# PixiFlood_1_8_PTH.net
KiCad netlist of a schematic drawn in EAGLE
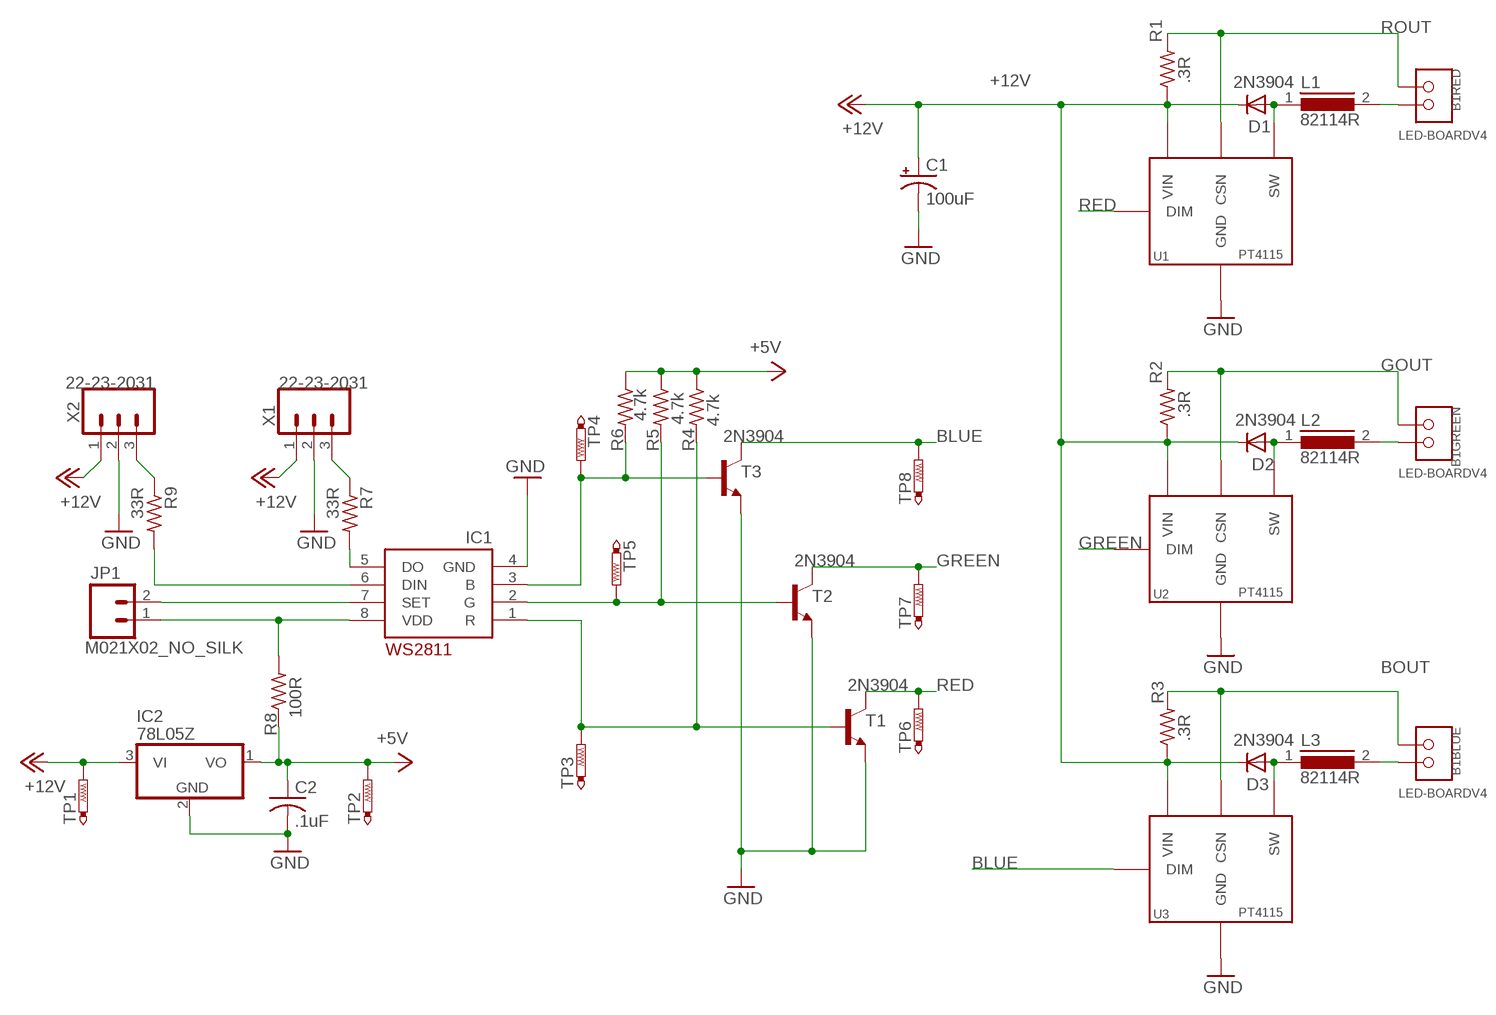
[diagram p0: schematic, sheet 1]

(export (version "E")
  (design (tool "Eeschema 10.0.6"))
  (components
    (comp (ref "B1")
      (value "LED-BOARDV4")
      (footprint "eagle-import:LED_BOARD-V4")
      (libsource (lib "eagle-import") (part "LED-BOARDV4"))
    )
    (comp (ref "C1")
      (value "100uF")
      (footprint "eagle-import:TT2D6L")
      (libsource (lib "eagle-import") (part "CPOL-USTT2D6L"))
    )
    (comp (ref "C2")
      (value ".1uF")
      (footprint "eagle-import:C050-024X044")
      (libsource (lib "eagle-import") (part "C-US050-024X044"))
    )
    (comp (ref "D1")
      (value "2N3904")
      (footprint "eagle-import:DO07")
      (libsource (lib "eagle-import") (part "DIODE-DO07"))
    )
    (comp (ref "D2")
      (value "2N3904")
      (footprint "eagle-import:DO07")
      (libsource (lib "eagle-import") (part "DIODE-DO07"))
    )
    (comp (ref "D3")
      (value "2N3904")
      (footprint "eagle-import:DO07")
      (libsource (lib "eagle-import") (part "DIODE-DO07"))
    )
    (comp (ref "IC1")
      (value "WS2811-SOP8")
      (footprint "eagle-import:SO08-SKINNYPADS")
      (libsource (lib "eagle-import") (part "WS2811-SOP8"))
    )
    (comp (ref "IC2")
      (value "78L05Z")
      (footprint "eagle-import:TO92")
      (libsource (lib "eagle-import") (part "78ZL05"))
    )
    (comp (ref "JP1")
      (value "M021X02_NO_SILK")
      (footprint "eagle-import:1X02_NO_SILK")
      (libsource (lib "eagle-import") (part "M021X02_NO_SILK"))
    )
    (comp (ref "L1")
      (value "82114R")
      (footprint "eagle-import:82114R")
      (libsource (lib "eagle-import") (part "82114R"))
    )
    (comp (ref "L2")
      (value "82114R")
      (footprint "eagle-import:82114R")
      (libsource (lib "eagle-import") (part "82114R"))
    )
    (comp (ref "L3")
      (value "82114R")
      (footprint "eagle-import:82114R")
      (libsource (lib "eagle-import") (part "82114R"))
    )
    (comp (ref "R1")
      (value ".3R")
      (footprint "eagle-import:0204_7")
      (libsource (lib "eagle-import") (part "resistor_R-US_0204/7"))
    )
    (comp (ref "R2")
      (value ".3R")
      (footprint "eagle-import:0204_7")
      (libsource (lib "eagle-import") (part "resistor_R-US_0204/7"))
    )
    (comp (ref "R3")
      (value ".3R")
      (footprint "eagle-import:0204_7")
      (libsource (lib "eagle-import") (part "resistor_R-US_0204/7"))
    )
    (comp (ref "R4")
      (value "4.7k")
      (footprint "eagle-import:0204_7")
      (libsource (lib "eagle-import") (part "resistor_R-US_0204/7"))
    )
    (comp (ref "R5")
      (value "4.7k")
      (footprint "eagle-import:0204_7")
      (libsource (lib "eagle-import") (part "resistor_R-US_0204/7"))
    )
    (comp (ref "R6")
      (value "4.7k")
      (footprint "eagle-import:0204_7")
      (libsource (lib "eagle-import") (part "resistor_R-US_0204/7"))
    )
    (comp (ref "R7")
      (value "33R")
      (footprint "eagle-import:0204_7")
      (libsource (lib "eagle-import") (part "R-US_0204/7"))
    )
    (comp (ref "R8")
      (value "100R")
      (footprint "eagle-import:0204_7")
      (libsource (lib "eagle-import") (part "R-US_0204/7"))
    )
    (comp (ref "R9")
      (value "33R")
      (footprint "eagle-import:0204_7")
      (libsource (lib "eagle-import") (part "R-US_0204/7"))
    )
    (comp (ref "T1")
      (value "2N3904")
      (footprint "eagle-import:TO92")
      (libsource (lib "eagle-import") (part "2N3904"))
    )
    (comp (ref "T2")
      (value "2N3904")
      (footprint "eagle-import:TO92")
      (libsource (lib "eagle-import") (part "2N3904"))
    )
    (comp (ref "T3")
      (value "2N3904")
      (footprint "eagle-import:TO92")
      (libsource (lib "eagle-import") (part "2N3904"))
    )
    (comp (ref "TP1")
      (value "PTR1B2,54")
      (footprint "eagle-import:B2,54")
      (libsource (lib "eagle-import") (part "PTR1B2,54"))
    )
    (comp (ref "TP2")
      (value "PTR1B2,54")
      (footprint "eagle-import:B2,54")
      (libsource (lib "eagle-import") (part "PTR1B2,54"))
    )
    (comp (ref "TP3")
      (value "PTR1B1,27")
      (footprint "eagle-import:B1,27")
      (libsource (lib "eagle-import") (part "PTR1B1,27"))
    )
    (comp (ref "TP4")
      (value "PTR1B1,27")
      (footprint "eagle-import:B1,27")
      (libsource (lib "eagle-import") (part "PTR1B1,27"))
    )
    (comp (ref "TP5")
      (value "PTR1B1,27")
      (footprint "eagle-import:B1,27")
      (libsource (lib "eagle-import") (part "PTR1B1,27"))
    )
    (comp (ref "TP6")
      (value "PTR1B1,27")
      (footprint "eagle-import:B1,27")
      (libsource (lib "eagle-import") (part "PTR1B1,27"))
    )
    (comp (ref "TP7")
      (value "PTR1B1,27")
      (footprint "eagle-import:B1,27")
      (libsource (lib "eagle-import") (part "PTR1B1,27"))
    )
    (comp (ref "TP8")
      (value "PTR1B1,27")
      (footprint "eagle-import:B1,27")
      (libsource (lib "eagle-import") (part "PTR1B1,27"))
    )
    (comp (ref "U1")
      (value "PT4115B89E")
      (footprint "eagle-import:SOT89-5")
      (libsource (lib "eagle-import") (part "PT4115B89E"))
    )
    (comp (ref "U2")
      (value "PT4115B89E")
      (footprint "eagle-import:SOT89-5")
      (libsource (lib "eagle-import") (part "PT4115B89E"))
    )
    (comp (ref "U3")
      (value "PT4115B89E")
      (footprint "eagle-import:SOT89-5")
      (libsource (lib "eagle-import") (part "PT4115B89E"))
    )
    (comp (ref "X1")
      (value "22-23-2031")
      (footprint "eagle-import:22-23-2031")
      (fields (field (name "MF") "MOLEX"))
      (libsource (lib "eagle-import") (part "22-23-2031"))
    )
    (comp (ref "X2")
      (value "22-23-2031")
      (footprint "eagle-import:22-23-2031")
      (fields (field (name "MF") "MOLEX"))
      (libsource (lib "eagle-import") (part "22-23-2031"))
    )
  )
  (nets
    (net (code "1") (name "+5V") (class "Default")
      (node (ref "C2") (pin "1") (pinfunction "1_1") (pintype "passive"))
      (node (ref "IC2") (pin "1") (pinfunction "VO_1") (pintype "passive"))
      (node (ref "R4") (pin "1") (pinfunction "1_1") (pintype "passive"))
      (node (ref "R5") (pin "1") (pinfunction "1_1") (pintype "passive"))
      (node (ref "R6") (pin "1") (pinfunction "1_1") (pintype "passive"))
      (node (ref "R8") (pin "1") (pinfunction "1_1") (pintype "passive"))
      (node (ref "TP2") (pin "TP") (pinfunction "TP_TP") (pintype "input"))
    )
    (net (code "2") (name "+12V") (class "Default")
      (node (ref "C1") (pin "+") (pinfunction "+_+") (pintype "passive"))
      (node (ref "D1") (pin "C") (pinfunction "C_C") (pintype "passive"))
      (node (ref "D2") (pin "C") (pinfunction "C_C") (pintype "passive"))
      (node (ref "D3") (pin "C") (pinfunction "C_C") (pintype "passive"))
      (node (ref "IC2") (pin "3") (pinfunction "VI_3") (pintype "input"))
      (node (ref "R1") (pin "1") (pinfunction "1_1") (pintype "passive"))
      (node (ref "R2") (pin "1") (pinfunction "1_1") (pintype "passive"))
      (node (ref "R3") (pin "1") (pinfunction "1_1") (pintype "passive"))
      (node (ref "TP1") (pin "TP") (pinfunction "TP_TP") (pintype "input"))
      (node (ref "U1") (pin "5") (pinfunction "VIN_5") (pintype "power_in"))
      (node (ref "U2") (pin "5") (pinfunction "VIN_5") (pintype "power_in"))
      (node (ref "U3") (pin "5") (pinfunction "VIN_5") (pintype "power_in"))
      (node (ref "X1") (pin "1") (pinfunction "1_1") (pintype "passive"))
      (node (ref "X2") (pin "1") (pinfunction "1_1") (pintype "passive"))
    )
    (net (code "3") (name "/BLUE") (class "Default")
      (node (ref "T3") (pin "1") (pinfunction "C_1") (pintype "passive"))
      (node (ref "TP8") (pin "TP") (pinfunction "TP_TP") (pintype "input"))
      (node (ref "U3") (pin "3") (pinfunction "DIM_3") (pintype "bidirectional"))
    )
    (net (code "4") (name "/BOUT") (class "Default")
      (node (ref "B1") (pin "B+") (pinfunction "P$2_B+") (pintype "bidirectional"))
      (node (ref "B1") (pin "B+@2") (pinfunction "P$2_B+@2") (pintype "bidirectional"))
      (node (ref "R3") (pin "2") (pinfunction "2_2") (pintype "passive"))
      (node (ref "U3") (pin "4") (pinfunction "CSN_4") (pintype "bidirectional"))
    )
    (net (code "5") (name "/GOUT") (class "Default")
      (node (ref "B1") (pin "G+") (pinfunction "P$2_G+") (pintype "bidirectional"))
      (node (ref "B1") (pin "G+@1") (pinfunction "P$2_G+@1") (pintype "bidirectional"))
      (node (ref "R2") (pin "2") (pinfunction "2_2") (pintype "passive"))
      (node (ref "U2") (pin "4") (pinfunction "CSN_4") (pintype "bidirectional"))
    )
    (net (code "6") (name "/GREEN") (class "Default")
      (node (ref "T2") (pin "1") (pinfunction "C_1") (pintype "passive"))
      (node (ref "TP7") (pin "TP") (pinfunction "TP_TP") (pintype "input"))
      (node (ref "U2") (pin "3") (pinfunction "DIM_3") (pintype "bidirectional"))
    )
    (net (code "7") (name "/RED") (class "Default")
      (node (ref "T1") (pin "1") (pinfunction "C_1") (pintype "passive"))
      (node (ref "TP6") (pin "TP") (pinfunction "TP_TP") (pintype "input"))
      (node (ref "U1") (pin "3") (pinfunction "DIM_3") (pintype "bidirectional"))
    )
    (net (code "8") (name "/ROUT") (class "Default")
      (node (ref "B1") (pin "R+") (pinfunction "P$2_R+") (pintype "bidirectional"))
      (node (ref "B1") (pin "R+@1") (pinfunction "P$2_R+@1") (pintype "bidirectional"))
      (node (ref "R1") (pin "2") (pinfunction "2_2") (pintype "passive"))
      (node (ref "U1") (pin "4") (pinfunction "CSN_4") (pintype "bidirectional"))
    )
    (net (code "9") (name "GND") (class "Default")
      (node (ref "C1") (pin "-") (pinfunction "-_-") (pintype "passive"))
      (node (ref "C2") (pin "2") (pinfunction "2_2") (pintype "passive"))
      (node (ref "IC1") (pin "4") (pinfunction "GND_4") (pintype "power_in"))
      (node (ref "IC2") (pin "2") (pinfunction "GND_2") (pintype "passive"))
      (node (ref "T1") (pin "3") (pinfunction "E_3") (pintype "passive"))
      (node (ref "T2") (pin "3") (pinfunction "E_3") (pintype "passive"))
      (node (ref "T3") (pin "3") (pinfunction "E_3") (pintype "passive"))
      (node (ref "U1") (pin "2") (pinfunction "GND_2") (pintype "power_in"))
      (node (ref "U1") (pin "2A") (pinfunction "GND_2A") (pintype "power_in"))
      (node (ref "U1") (pin "2A@1") (pinfunction "GND_2A@1") (pintype "power_in"))
      (node (ref "U1") (pin "2A@3") (pinfunction "GND_2A@3") (pintype "power_in"))
      (node (ref "U1") (pin "2A@4") (pinfunction "GND_2A@4") (pintype "power_in"))
      (node (ref "U2") (pin "2") (pinfunction "GND_2") (pintype "power_in"))
      (node (ref "U2") (pin "2A") (pinfunction "GND_2A") (pintype "power_in"))
      (node (ref "U2") (pin "2A@1") (pinfunction "GND_2A@1") (pintype "power_in"))
      (node (ref "U2") (pin "2A@3") (pinfunction "GND_2A@3") (pintype "power_in"))
      (node (ref "U2") (pin "2A@4") (pinfunction "GND_2A@4") (pintype "power_in"))
      (node (ref "U3") (pin "2") (pinfunction "GND_2") (pintype "power_in"))
      (node (ref "U3") (pin "2A") (pinfunction "GND_2A") (pintype "power_in"))
      (node (ref "U3") (pin "2A@1") (pinfunction "GND_2A@1") (pintype "power_in"))
      (node (ref "U3") (pin "2A@3") (pinfunction "GND_2A@3") (pintype "power_in"))
      (node (ref "U3") (pin "2A@4") (pinfunction "GND_2A@4") (pintype "power_in"))
      (node (ref "X1") (pin "2") (pinfunction "2_2") (pintype "passive"))
      (node (ref "X2") (pin "2") (pinfunction "2_2") (pintype "passive"))
    )
    (net (code "10") (name "Net-(B1A-P$1-PadB-)") (class "Default")
      (node (ref "B1") (pin "B-") (pinfunction "P$1_B-") (pintype "bidirectional"))
      (node (ref "B1") (pin "B-@1") (pinfunction "P$1_B-@1") (pintype "bidirectional"))
      (node (ref "L3") (pin "2") (pinfunction "2_2") (pintype "passive"))
    )
    (net (code "11") (name "Net-(B1B-P$1-PadG-)") (class "Default")
      (node (ref "B1") (pin "G-") (pinfunction "P$1_G-") (pintype "bidirectional"))
      (node (ref "B1") (pin "G-@1") (pinfunction "P$1_G-@1") (pintype "bidirectional"))
      (node (ref "L2") (pin "2") (pinfunction "2_2") (pintype "passive"))
    )
    (net (code "12") (name "Net-(B1C-P$1-PadR-)") (class "Default")
      (node (ref "B1") (pin "R-") (pinfunction "P$1_R-") (pintype "bidirectional"))
      (node (ref "B1") (pin "R-@1") (pinfunction "P$1_R-@1") (pintype "bidirectional"))
      (node (ref "L1") (pin "2") (pinfunction "2_2") (pintype "passive"))
    )
    (net (code "13") (name "Net-(IC1-B)") (class "Default")
      (node (ref "IC1") (pin "3") (pinfunction "B_3") (pintype "open_collector"))
      (node (ref "R6") (pin "2") (pinfunction "2_2") (pintype "passive"))
      (node (ref "T3") (pin "2") (pinfunction "B_2") (pintype "passive"))
      (node (ref "TP4") (pin "TP") (pinfunction "TP_TP") (pintype "input"))
    )
    (net (code "14") (name "Net-(IC1-DIN)") (class "Default")
      (node (ref "IC1") (pin "6") (pinfunction "DIN_6") (pintype "input"))
      (node (ref "R9") (pin "2") (pinfunction "2_2") (pintype "passive"))
    )
    (net (code "15") (name "Net-(IC1-DO)") (class "Default")
      (node (ref "IC1") (pin "5") (pinfunction "DO_5") (pintype "output"))
      (node (ref "R7") (pin "2") (pinfunction "2_2") (pintype "passive"))
    )
    (net (code "16") (name "Net-(IC1-G)") (class "Default")
      (node (ref "IC1") (pin "2") (pinfunction "G_2") (pintype "open_collector"))
      (node (ref "R5") (pin "2") (pinfunction "2_2") (pintype "passive"))
      (node (ref "T2") (pin "2") (pinfunction "B_2") (pintype "passive"))
      (node (ref "TP5") (pin "TP") (pinfunction "TP_TP") (pintype "input"))
    )
    (net (code "17") (name "Net-(IC1-R)") (class "Default")
      (node (ref "IC1") (pin "1") (pinfunction "R_1") (pintype "open_collector"))
      (node (ref "R4") (pin "2") (pinfunction "2_2") (pintype "passive"))
      (node (ref "T1") (pin "2") (pinfunction "B_2") (pintype "passive"))
      (node (ref "TP3") (pin "TP") (pinfunction "TP_TP") (pintype "input"))
    )
    (net (code "18") (name "Net-(IC1-SET)") (class "Default")
      (node (ref "IC1") (pin "7") (pinfunction "SET_7") (pintype "input"))
      (node (ref "JP1") (pin "2") (pinfunction "2_2") (pintype "passive"))
    )
    (net (code "19") (name "Net-(IC1-VDD)") (class "Default")
      (node (ref "IC1") (pin "8") (pinfunction "VDD_8") (pintype "power_in"))
      (node (ref "JP1") (pin "1") (pinfunction "1_1") (pintype "passive"))
      (node (ref "R8") (pin "2") (pinfunction "2_2") (pintype "passive"))
    )
    (net (code "20") (name "Net-(R7-Pad1)") (class "Default")
      (node (ref "R7") (pin "1") (pinfunction "1_1") (pintype "passive"))
      (node (ref "X1") (pin "3") (pinfunction "3_3") (pintype "passive"))
    )
    (net (code "21") (name "Net-(R9-Pad1)") (class "Default")
      (node (ref "R9") (pin "1") (pinfunction "1_1") (pintype "passive"))
      (node (ref "X2") (pin "3") (pinfunction "3_3") (pintype "passive"))
    )
    (net (code "22") (name "Net-(U1-SW)") (class "Default")
      (node (ref "D1") (pin "A") (pinfunction "A_A") (pintype "passive"))
      (node (ref "L1") (pin "1") (pinfunction "1_1") (pintype "passive"))
      (node (ref "U1") (pin "1") (pinfunction "SW_1") (pintype "bidirectional"))
    )
    (net (code "23") (name "Net-(U2-SW)") (class "Default")
      (node (ref "D2") (pin "A") (pinfunction "A_A") (pintype "passive"))
      (node (ref "L2") (pin "1") (pinfunction "1_1") (pintype "passive"))
      (node (ref "U2") (pin "1") (pinfunction "SW_1") (pintype "bidirectional"))
    )
    (net (code "24") (name "Net-(U3-SW)") (class "Default")
      (node (ref "D3") (pin "A") (pinfunction "A_A") (pintype "passive"))
      (node (ref "L3") (pin "1") (pinfunction "1_1") (pintype "passive"))
      (node (ref "U3") (pin "1") (pinfunction "SW_1") (pintype "bidirectional"))
    )
  )
)
